# Motor_Board.net
KiCad netlist of a schematic drawn in EAGLE
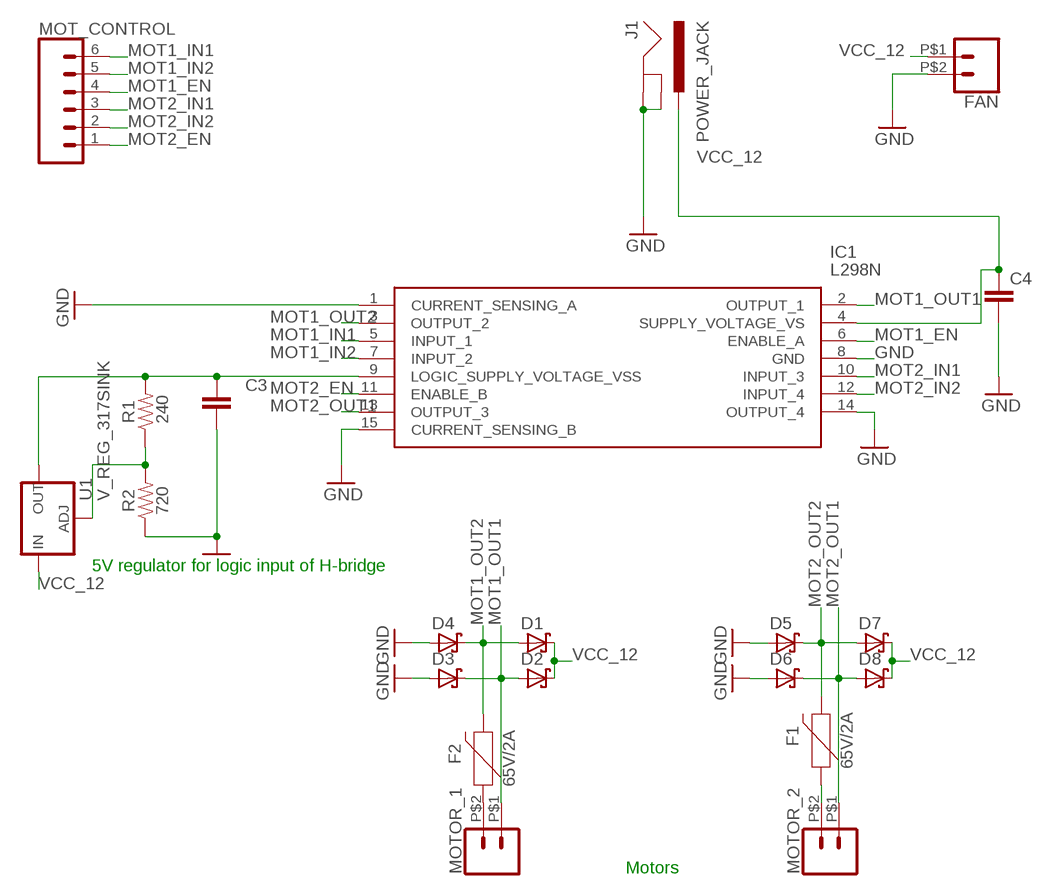
[diagram p0: schematic, sheet 1]

(export (version "E")
  (design (tool "Eeschema 10.0.6"))
  (components
    (comp (ref "C3")
      (value "C5/5")
      (footprint "eagle-import:C5B5")
      (libsource (lib "eagle-import") (part "C5/5"))
    )
    (comp (ref "C4")
      (value "C5/5")
      (footprint "eagle-import:C5B5")
      (libsource (lib "eagle-import") (part "C5/5"))
    )
    (comp (ref "D1")
      (value "SCHOTTKY-DIODEC4111-15")
      (footprint "eagle-import:C4111-15")
      (libsource (lib "eagle-import") (part "SCHOTTKY-DIODEC4111-15"))
    )
    (comp (ref "D2")
      (value "SCHOTTKY-DIODEC4111-15")
      (footprint "eagle-import:C4111-15")
      (libsource (lib "eagle-import") (part "SCHOTTKY-DIODEC4111-15"))
    )
    (comp (ref "D3")
      (value "SCHOTTKY-DIODEC4111-15")
      (footprint "eagle-import:C4111-15")
      (libsource (lib "eagle-import") (part "SCHOTTKY-DIODEC4111-15"))
    )
    (comp (ref "D4")
      (value "SCHOTTKY-DIODEC4111-15")
      (footprint "eagle-import:C4111-15")
      (libsource (lib "eagle-import") (part "SCHOTTKY-DIODEC4111-15"))
    )
    (comp (ref "D5")
      (value "SCHOTTKY-DIODEC4111-15")
      (footprint "eagle-import:C4111-15")
      (libsource (lib "eagle-import") (part "SCHOTTKY-DIODEC4111-15"))
    )
    (comp (ref "D6")
      (value "SCHOTTKY-DIODEC4111-15")
      (footprint "eagle-import:C4111-15")
      (libsource (lib "eagle-import") (part "SCHOTTKY-DIODEC4111-15"))
    )
    (comp (ref "D7")
      (value "SCHOTTKY-DIODEC4111-15")
      (footprint "eagle-import:C4111-15")
      (libsource (lib "eagle-import") (part "SCHOTTKY-DIODEC4111-15"))
    )
    (comp (ref "D8")
      (value "SCHOTTKY-DIODEC4111-15")
      (footprint "eagle-import:C4111-15")
      (libsource (lib "eagle-import") (part "SCHOTTKY-DIODEC4111-15"))
    )
    (comp (ref "F1")
      (value "65V/2A")
      (footprint "eagle-import:PTH")
      (libsource (lib "eagle-import") (part "PPTC_PTH"))
    )
    (comp (ref "F2")
      (value "65V/2A")
      (footprint "eagle-import:PTH")
      (libsource (lib "eagle-import") (part "PPTC_PTH"))
    )
    (comp (ref "FAN")
      (value "CONN_02PTH2")
      (footprint "eagle-import:1X02_BIG")
      (libsource (lib "eagle-import") (part "CONN_02PTH2"))
    )
    (comp (ref "IC1")
      (value "L298N")
      (footprint "eagle-import:MULTIWATT15V_1")
      (fields (field (name "RS_PART_NUMBER") "0636384"))
      (libsource (lib "eagle-import") (part "L298N"))
    )
    (comp (ref "J1")
      (value "POWER_JACK")
      (footprint "eagle-import:POWER_JACK_PTH")
      (libsource (lib "eagle-import") (part "POWER_JACK"))
    )
    (comp (ref "MOTOR_1")
      (value "CONN_02PTH2")
      (footprint "eagle-import:1X02_BIG")
      (libsource (lib "eagle-import") (part "CONN_02PTH2"))
    )
    (comp (ref "MOTOR_2")
      (value "CONN_02PTH2")
      (footprint "eagle-import:1X02_BIG")
      (libsource (lib "eagle-import") (part "CONN_02PTH2"))
    )
    (comp (ref "MOT_CONTROL")
      (value "CONN_06SILK_FEMALE_PTH")
      (footprint "eagle-import:1X06")
      (libsource (lib "eagle-import") (part "CONN_06SILK_FEMALE_PTH"))
    )
    (comp (ref "R1")
      (value "240")
      (footprint "eagle-import:AXIAL-0.3")
      (libsource (lib "eagle-import") (part "RESISTORAXIAL-0.3"))
    )
    (comp (ref "R2")
      (value "720")
      (footprint "eagle-import:AXIAL-0.3")
      (libsource (lib "eagle-import") (part "RESISTORAXIAL-0.3"))
    )
    (comp (ref "U1")
      (value "V_REG_317SINK")
      (footprint "eagle-import:TO220-ADJ")
      (libsource (lib "eagle-import") (part "V_REG_317SINK"))
    )
  )
  (nets
    (net (code "1") (name "/MOT1_EN") (class "Default")
      (node (ref "IC1") (pin "6") (pinfunction "ENABLE_A_6") (pintype "bidirectional"))
      (node (ref "MOT_CONTROL") (pin "4") (pinfunction "4_4") (pintype "passive"))
    )
    (net (code "2") (name "/MOT1_IN1") (class "Default")
      (node (ref "IC1") (pin "5") (pinfunction "INPUT_1_5") (pintype "bidirectional"))
      (node (ref "MOT_CONTROL") (pin "6") (pinfunction "6_6") (pintype "passive"))
    )
    (net (code "3") (name "/MOT1_IN2") (class "Default")
      (node (ref "IC1") (pin "7") (pinfunction "INPUT_2_7") (pintype "bidirectional"))
      (node (ref "MOT_CONTROL") (pin "5") (pinfunction "5_5") (pintype "passive"))
    )
    (net (code "4") (name "/MOT1_OUT1") (class "Default")
      (node (ref "D2") (pin "A") (pinfunction "A_A") (pintype "passive"))
      (node (ref "D3") (pin "C") (pinfunction "C_C") (pintype "passive"))
      (node (ref "IC1") (pin "2") (pinfunction "OUTPUT_1_2") (pintype "bidirectional"))
      (node (ref "MOTOR_1") (pin "P$1") (pinfunction "1_P$1") (pintype "passive"))
    )
    (net (code "5") (name "/MOT1_OUT2") (class "Default")
      (node (ref "D1") (pin "A") (pinfunction "A_A") (pintype "passive"))
      (node (ref "D4") (pin "C") (pinfunction "C_C") (pintype "passive"))
      (node (ref "F2") (pin "P$2") (pinfunction "2_P$2") (pintype "bidirectional"))
      (node (ref "IC1") (pin "3") (pinfunction "OUTPUT_2_3") (pintype "bidirectional"))
    )
    (net (code "6") (name "/MOT2_EN") (class "Default")
      (node (ref "IC1") (pin "11") (pinfunction "ENABLE_B_11") (pintype "bidirectional"))
      (node (ref "MOT_CONTROL") (pin "1") (pinfunction "1_1") (pintype "passive"))
    )
    (net (code "7") (name "/MOT2_IN1") (class "Default")
      (node (ref "IC1") (pin "10") (pinfunction "INPUT_3_10") (pintype "bidirectional"))
      (node (ref "MOT_CONTROL") (pin "3") (pinfunction "3_3") (pintype "passive"))
    )
    (net (code "8") (name "/MOT2_IN2") (class "Default")
      (node (ref "IC1") (pin "12") (pinfunction "INPUT_4_12") (pintype "bidirectional"))
      (node (ref "MOT_CONTROL") (pin "2") (pinfunction "2_2") (pintype "passive"))
    )
    (net (code "9") (name "/MOT2_OUT1") (class "Default")
      (node (ref "D6") (pin "C") (pinfunction "C_C") (pintype "passive"))
      (node (ref "D8") (pin "A") (pinfunction "A_A") (pintype "passive"))
      (node (ref "IC1") (pin "13") (pinfunction "OUTPUT_3_13") (pintype "bidirectional"))
      (node (ref "MOTOR_2") (pin "P$1") (pinfunction "1_P$1") (pintype "passive"))
    )
    (net (code "10") (name "/MOT2_OUT2") (class "Default")
      (node (ref "D5") (pin "C") (pinfunction "C_C") (pintype "passive"))
      (node (ref "D7") (pin "A") (pinfunction "A_A") (pintype "passive"))
      (node (ref "F1") (pin "P$2") (pinfunction "2_P$2") (pintype "bidirectional"))
    )
    (net (code "11") (name "/VCC_12") (class "Default")
      (node (ref "C4") (pin "1") (pinfunction "1_1") (pintype "passive"))
      (node (ref "D1") (pin "C") (pinfunction "C_C") (pintype "passive"))
      (node (ref "D2") (pin "C") (pinfunction "C_C") (pintype "passive"))
      (node (ref "D7") (pin "C") (pinfunction "C_C") (pintype "passive"))
      (node (ref "D8") (pin "C") (pinfunction "C_C") (pintype "passive"))
      (node (ref "FAN") (pin "P$1") (pinfunction "1_P$1") (pintype "passive"))
      (node (ref "IC1") (pin "4") (pinfunction "SUPPLY_VOLTAGE_VS_4") (pintype "bidirectional"))
      (node (ref "J1") (pin "PWR") (pinfunction "PWR_PWR") (pintype "bidirectional"))
      (node (ref "U1") (pin "IN") (pinfunction "IN_IN") (pintype "input"))
    )
    (net (code "12") (name "GND") (class "Default")
      (node (ref "C3") (pin "2") (pinfunction "2_2") (pintype "passive"))
      (node (ref "C4") (pin "2") (pinfunction "2_2") (pintype "passive"))
      (node (ref "D3") (pin "A") (pinfunction "A_A") (pintype "passive"))
      (node (ref "D4") (pin "A") (pinfunction "A_A") (pintype "passive"))
      (node (ref "D5") (pin "A") (pinfunction "A_A") (pintype "passive"))
      (node (ref "D6") (pin "A") (pinfunction "A_A") (pintype "passive"))
      (node (ref "FAN") (pin "P$2") (pinfunction "2_P$2") (pintype "passive"))
      (node (ref "IC1") (pin "1") (pinfunction "CURRENT_SENSING_A_1") (pintype "bidirectional"))
      (node (ref "IC1") (pin "14") (pinfunction "OUTPUT_4_14") (pintype "bidirectional"))
      (node (ref "IC1") (pin "15") (pinfunction "CURRENT_SENSING_B_15") (pintype "bidirectional"))
      (node (ref "IC1") (pin "8") (pinfunction "GND_8") (pintype "bidirectional"))
      (node (ref "J1") (pin "GND") (pinfunction "GND_GND") (pintype "bidirectional"))
      (node (ref "J1") (pin "GNDBREAK") (pinfunction "GNDBREAK_GNDBREAK") (pintype "bidirectional"))
      (node (ref "R2") (pin "P$1") (pinfunction "1_P$1") (pintype "passive"))
    )
    (net (code "13") (name "Net-(F1-1)") (class "Default")
      (node (ref "F1") (pin "P$1") (pinfunction "1_P$1") (pintype "bidirectional"))
      (node (ref "MOTOR_2") (pin "P$2") (pinfunction "2_P$2") (pintype "passive"))
    )
    (net (code "14") (name "Net-(F2-1)") (class "Default")
      (node (ref "F2") (pin "P$1") (pinfunction "1_P$1") (pintype "bidirectional"))
      (node (ref "MOTOR_1") (pin "P$2") (pinfunction "2_P$2") (pintype "passive"))
    )
    (net (code "15") (name "Net-(IC1-LOGIC_SUPPLY_VOLTAGE_VSS)") (class "Default")
      (node (ref "C3") (pin "1") (pinfunction "1_1") (pintype "passive"))
      (node (ref "IC1") (pin "9") (pinfunction "LOGIC_SUPPLY_VOLTAGE_VSS_9") (pintype "bidirectional"))
      (node (ref "R1") (pin "P$2") (pinfunction "2_P$2") (pintype "passive"))
      (node (ref "U1") (pin "OUT") (pinfunction "OUT_OUT") (pintype "output"))
    )
    (net (code "16") (name "Net-(R1-1)") (class "Default")
      (node (ref "R1") (pin "P$1") (pinfunction "1_P$1") (pintype "passive"))
      (node (ref "R2") (pin "P$2") (pinfunction "2_P$2") (pintype "passive"))
      (node (ref "U1") (pin "ADJ") (pinfunction "ADJ_ADJ") (pintype "input"))
    )
  )
)
